# Roboteq_IO_Board_V2.net
KiCad netlist of a schematic drawn in EAGLE
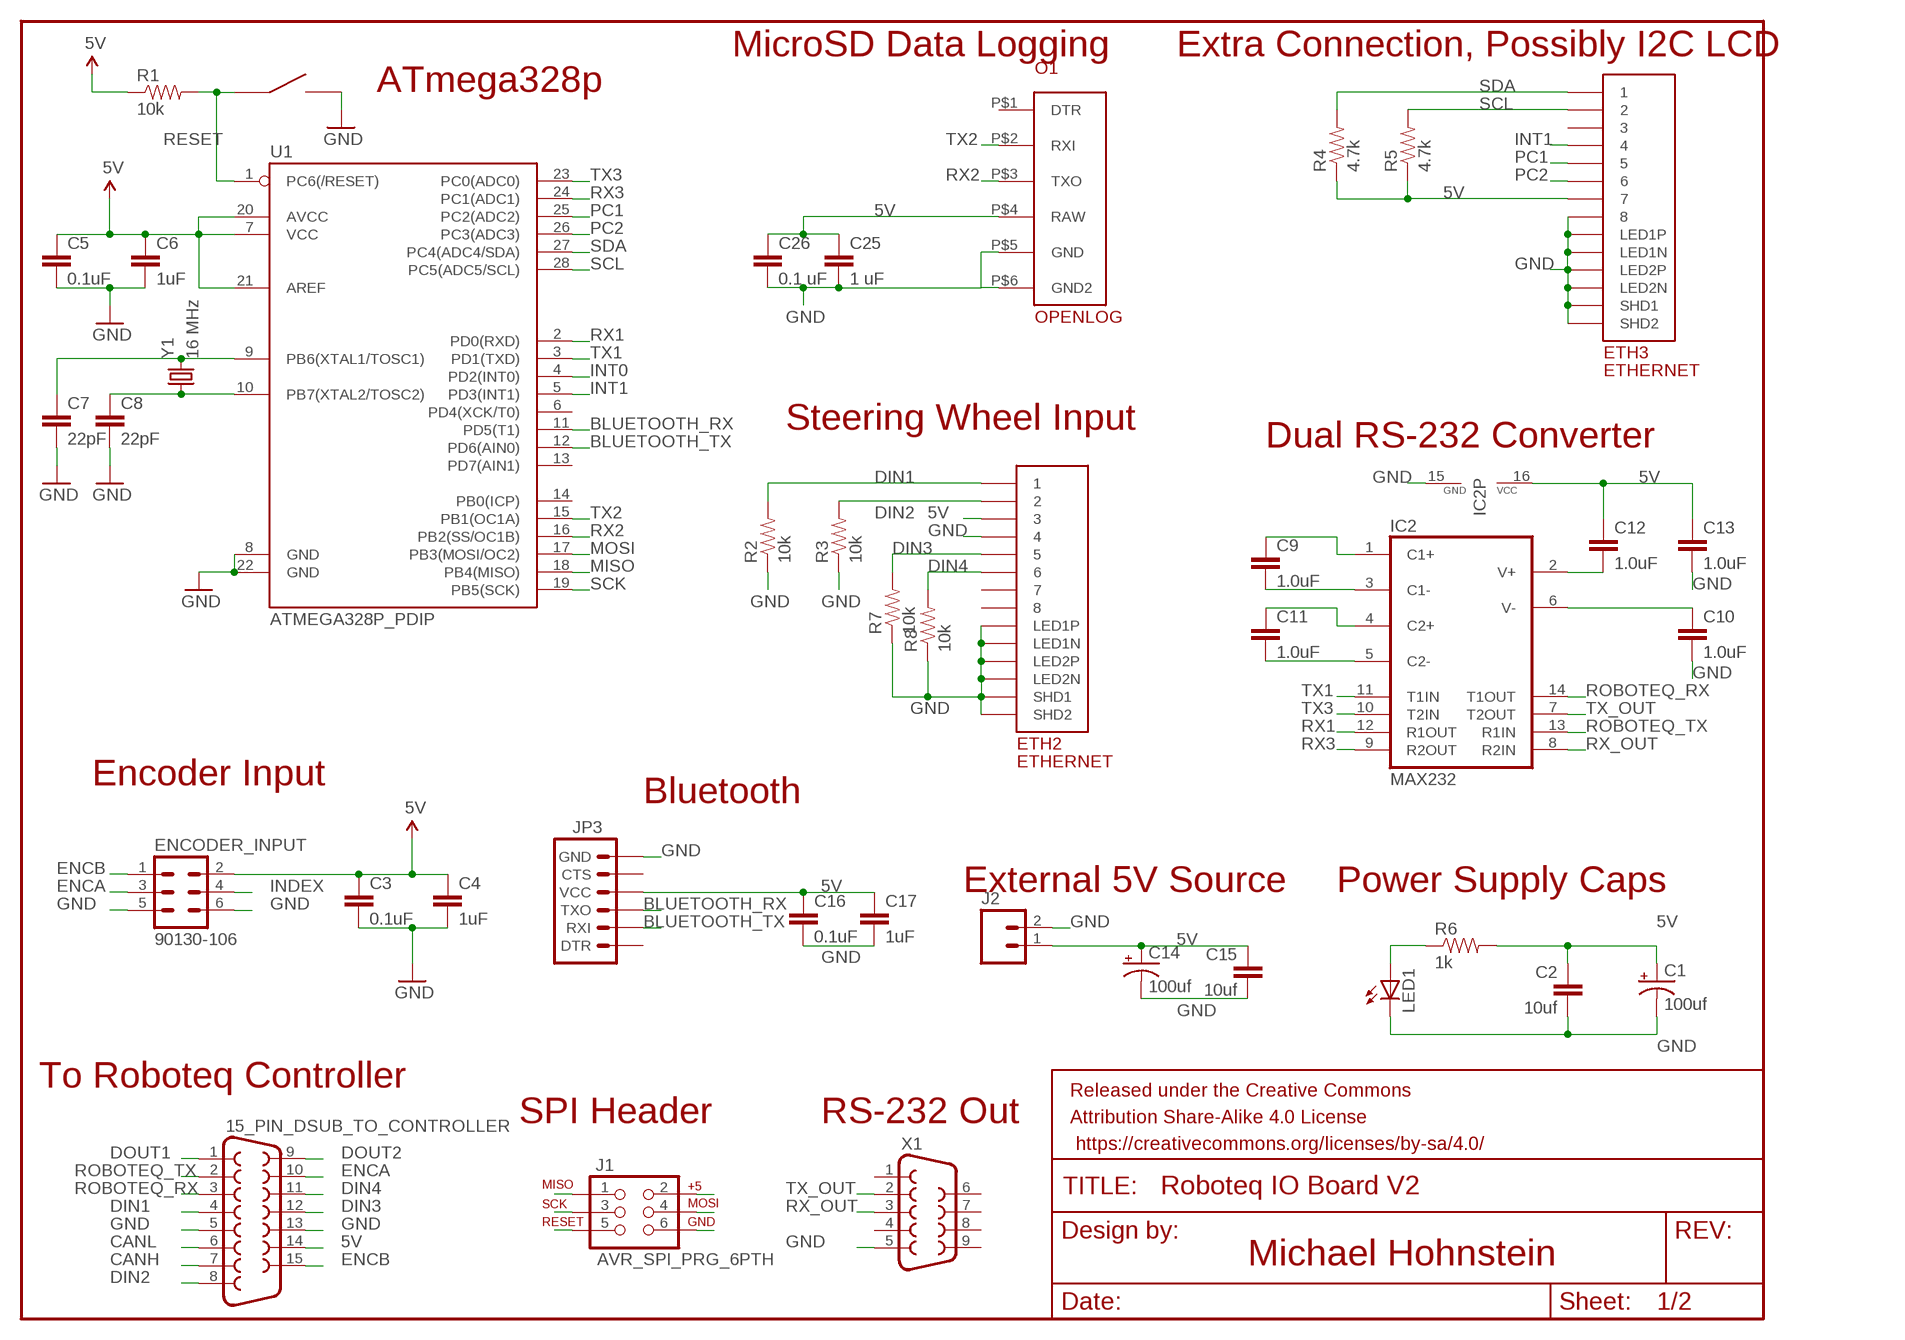
[diagram p0: schematic, sheet 1]
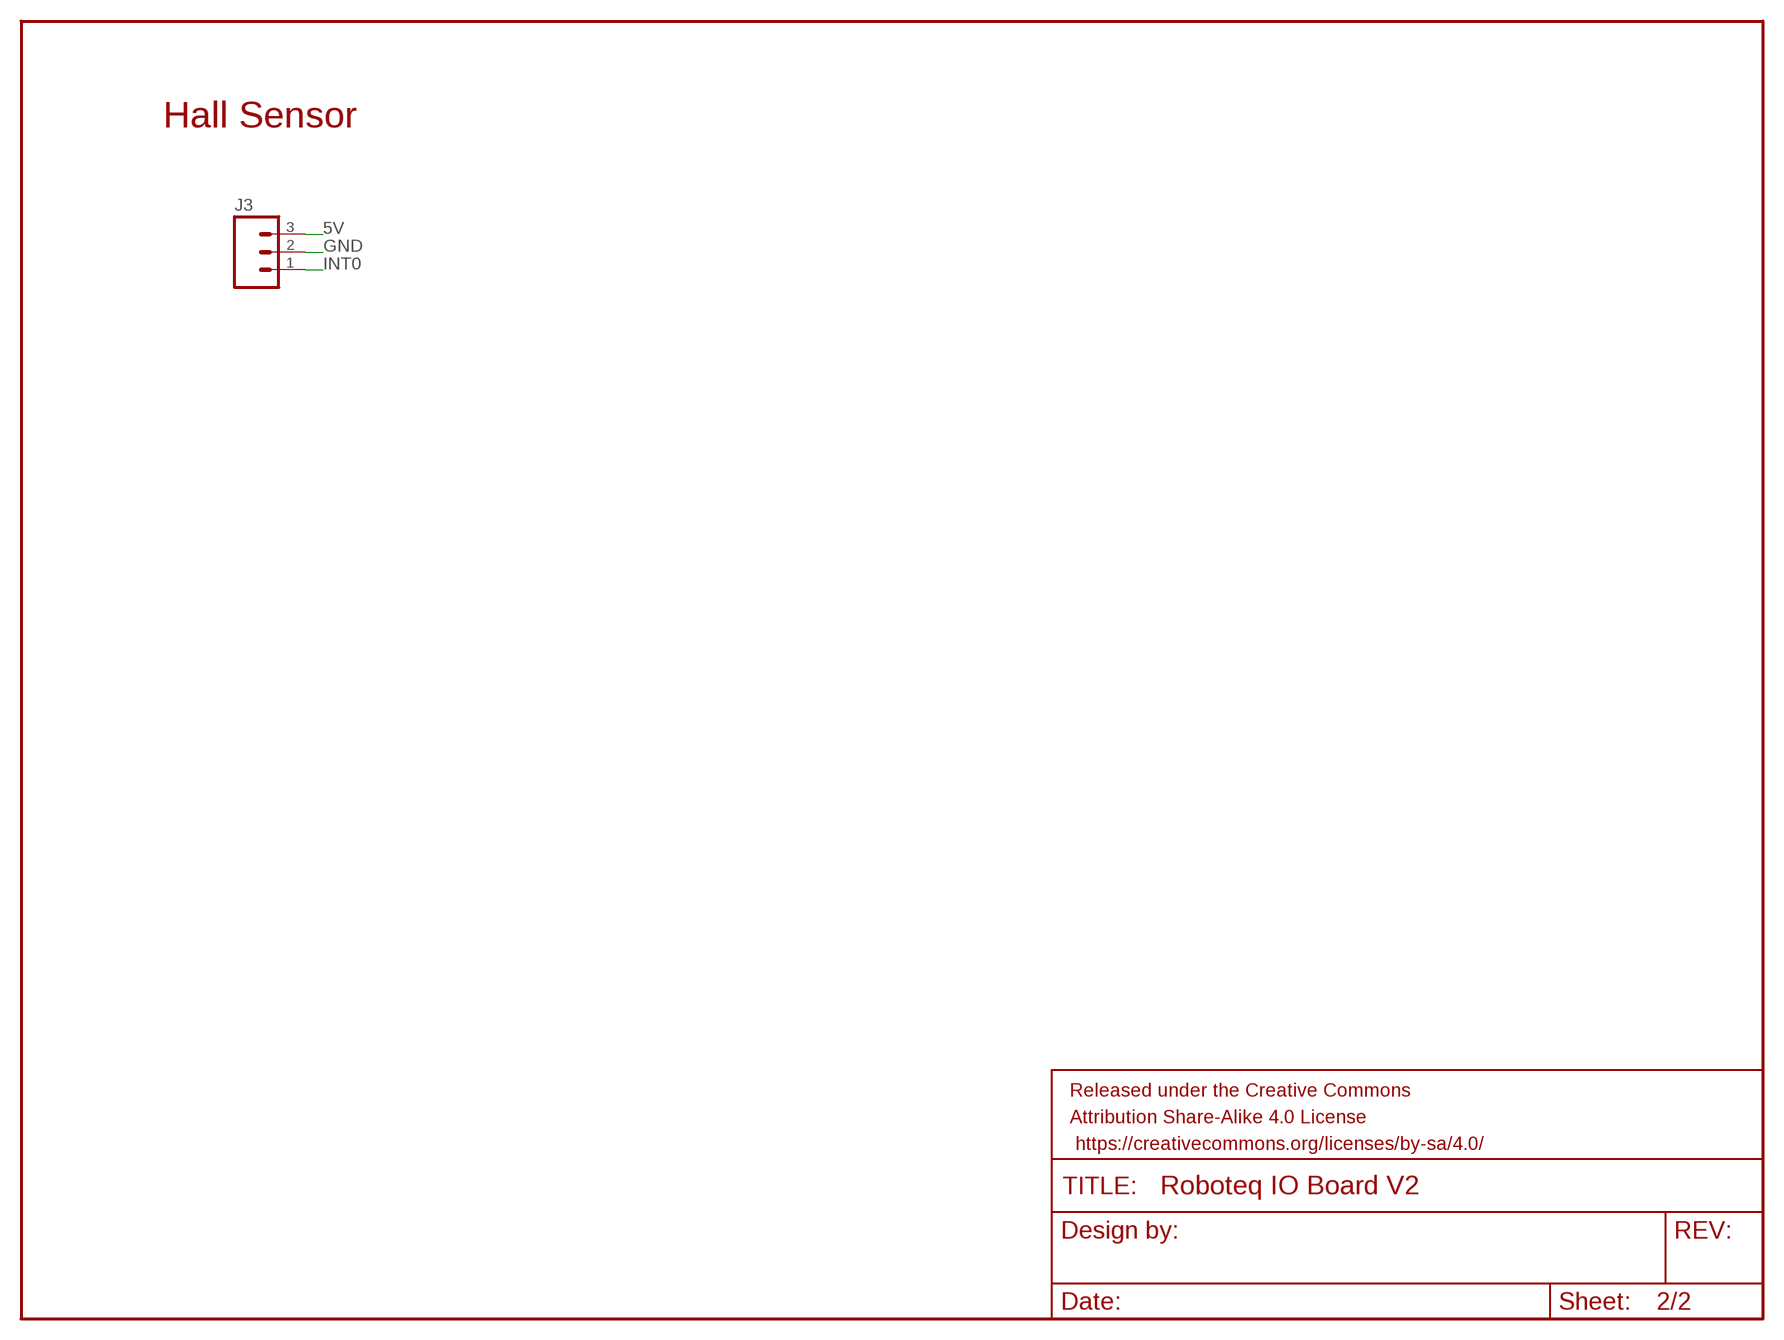
[diagram p1: schematic, sheet 2]

(export (version "E")
  (design (tool "Eeschema 10.0.6"))
  (components
    (comp (ref "15_PIN_DSUB_TO_CONTROLLER")
      (value "F15HP")
      (footprint "eagle-import:F15HP")
      (libsource (lib "eagle-import") (part "F15HP"))
    )
    (comp (ref "C1")
      (value "100uf")
      (footprint "eagle-import:PANASONIC_C")
      (libsource (lib "eagle-import") (part "CAP_POLC"))
    )
    (comp (ref "C2")
      (value "10uf")
      (footprint "eagle-import:0805")
      (libsource (lib "eagle-import") (part "CAP0805"))
    )
    (comp (ref "C3")
      (value "0.1uF")
      (footprint "eagle-import:0805")
      (libsource (lib "eagle-import") (part "CAP0805"))
    )
    (comp (ref "C4")
      (value "1uF")
      (footprint "eagle-import:0805")
      (libsource (lib "eagle-import") (part "CAP0805"))
    )
    (comp (ref "C5")
      (value "0.1uF")
      (footprint "eagle-import:0805")
      (libsource (lib "eagle-import") (part "CAP0805"))
    )
    (comp (ref "C6")
      (value "1uF")
      (footprint "eagle-import:0805")
      (libsource (lib "eagle-import") (part "CAP0805"))
    )
    (comp (ref "C7")
      (value "22pF")
      (footprint "eagle-import:0805")
      (libsource (lib "eagle-import") (part "SparkFun-Passives_CAP0805"))
    )
    (comp (ref "C8")
      (value "22pF")
      (footprint "eagle-import:0805")
      (libsource (lib "eagle-import") (part "SparkFun-Passives_CAP0805"))
    )
    (comp (ref "C9")
      (value "1.0uF")
      (footprint "eagle-import:0805")
      (libsource (lib "eagle-import") (part "CAP0805"))
    )
    (comp (ref "C10")
      (value "1.0uF")
      (footprint "eagle-import:0805")
      (libsource (lib "eagle-import") (part "CAP0805"))
    )
    (comp (ref "C11")
      (value "1.0uF")
      (footprint "eagle-import:0805")
      (libsource (lib "eagle-import") (part "CAP0805"))
    )
    (comp (ref "C12")
      (value "1.0uF")
      (footprint "eagle-import:0805")
      (libsource (lib "eagle-import") (part "CAP0805"))
    )
    (comp (ref "C13")
      (value "1.0uF")
      (footprint "eagle-import:0805")
      (libsource (lib "eagle-import") (part "CAP0805"))
    )
    (comp (ref "C14")
      (value "100uf")
      (footprint "eagle-import:PANASONIC_C")
      (libsource (lib "eagle-import") (part "CAP_POLC"))
    )
    (comp (ref "C15")
      (value "10uf")
      (footprint "eagle-import:0805")
      (libsource (lib "eagle-import") (part "CAP0805"))
    )
    (comp (ref "C16")
      (value "0.1uF")
      (footprint "eagle-import:0805")
      (libsource (lib "eagle-import") (part "CAP0805"))
    )
    (comp (ref "C17")
      (value "1uF")
      (footprint "eagle-import:0805")
      (libsource (lib "eagle-import") (part "CAP0805"))
    )
    (comp (ref "C25")
      (value "1 uF")
      (footprint "eagle-import:0805")
      (libsource (lib "eagle-import") (part "CAP0805"))
    )
    (comp (ref "C26")
      (value "0.1 uF")
      (footprint "eagle-import:0805")
      (libsource (lib "eagle-import") (part "CAP0805"))
    )
    (comp (ref "ENCODER_INPUT")
      (value "90130-106")
      (footprint "eagle-import:90130-1_06")
      (libsource (lib "eagle-import") (part "90130-1?06"))
    )
    (comp (ref "ETH2")
      (value "ETHERNET")
      (footprint "eagle-import:A122645-ND")
      (libsource (lib "eagle-import") (part "ETHERNET"))
    )
    (comp (ref "ETH3")
      (value "ETHERNET")
      (footprint "eagle-import:A122645-ND")
      (libsource (lib "eagle-import") (part "ETHERNET"))
    )
    (comp (ref "FRAME2")
      (value "FRAME-LETTER")
      (footprint "eagle-import:CREATIVE_COMMONS")
      (libsource (lib "eagle-import") (part "FRAME-LETTER"))
    )
    (comp (ref "IC2")
      (value "MAX232")
      (footprint "eagle-import:DIL16")
      (fields (field (name "MF") "MAXIM") (field (name "MPN") "MAX232ACPE+"))
      (libsource (lib "eagle-import") (part "MAX232"))
    )
    (comp (ref "J1")
      (value "AVR_SPI_PRG_6PTH")
      (footprint "eagle-import:2X3")
      (libsource (lib "eagle-import") (part "AVR_SPI_PRG_6PTH"))
    )
    (comp (ref "J2")
      (value "M02PTH")
      (footprint "eagle-import:1X02")
      (libsource (lib "eagle-import") (part "M02PTH"))
    )
    (comp (ref "JP3")
      (value "ARDUINO_SERIAL_PROGRAMPTH")
      (footprint "eagle-import:1X06")
      (libsource (lib "eagle-import") (part "ARDUINO_SERIAL_PROGRAMPTH"))
    )
    (comp (ref "LED1")
      (value "LEDCHIP-LED0805")
      (footprint "eagle-import:CHIP-LED0805")
      (libsource (lib "eagle-import") (part "LEDCHIP-LED0805"))
    )
    (comp (ref "O1")
      (value "OPENLOG")
      (footprint "eagle-import:OPENLOG")
      (libsource (lib "eagle-import") (part "OPENLOG"))
    )
    (comp (ref "R1")
      (value "10k")
      (footprint "eagle-import:0805")
      (libsource (lib "eagle-import") (part "RESISTOR0805-RES"))
    )
    (comp (ref "R2")
      (value "10k")
      (footprint "eagle-import:0805")
      (libsource (lib "eagle-import") (part "RESISTOR0805-RES"))
    )
    (comp (ref "R3")
      (value "10k")
      (footprint "eagle-import:0805")
      (libsource (lib "eagle-import") (part "RESISTOR0805-RES"))
    )
    (comp (ref "R4")
      (value "4.7k")
      (footprint "eagle-import:0805")
      (libsource (lib "eagle-import") (part "RESISTOR0805-RES"))
    )
    (comp (ref "R5")
      (value "4.7k")
      (footprint "eagle-import:0805")
      (libsource (lib "eagle-import") (part "RESISTOR0805-RES"))
    )
    (comp (ref "R6")
      (value "1k")
      (footprint "eagle-import:0805")
      (libsource (lib "eagle-import") (part "RESISTOR0805-RES"))
    )
    (comp (ref "R7")
      (value "10k")
      (footprint "eagle-import:0805")
      (libsource (lib "eagle-import") (part "RESISTOR0805-RES"))
    )
    (comp (ref "R8")
      (value "10k")
      (footprint "eagle-import:0805")
      (libsource (lib "eagle-import") (part "RESISTOR0805-RES"))
    )
    (comp (ref "U$3")
      (value "EG4621CT-ND")
      (footprint "eagle-import:EG4621CT-ND")
      (libsource (lib "eagle-import") (part "EG4621CT-ND"))
    )
    (comp (ref "U1")
      (value "ATMEGA328P_PDIP")
      (footprint "eagle-import:DIL28-3")
      (libsource (lib "eagle-import") (part "ATMEGA328P_PDIP"))
    )
    (comp (ref "X1")
      (value "F09HP")
      (footprint "eagle-import:F09HP")
      (libsource (lib "eagle-import") (part "F09HP"))
    )
    (comp (ref "Y1")
      (value "16 MHz")
      (footprint "eagle-import:HC49US")
      (libsource (lib "eagle-import") (part "CRYSTALHC49US"))
    )
    (comp (ref "FRAME1")
      (value "FRAME-LETTER")
      (footprint "eagle-import:CREATIVE_COMMONS")
      (libsource (lib "eagle-import") (part "FRAME-LETTER"))
    )
    (comp (ref "J3")
      (value "M03PTH")
      (footprint "eagle-import:1X03")
      (libsource (lib "eagle-import") (part "M03PTH"))
    )
  )
  (nets
    (net (code "1") (name "5V") (class "Default")
      (node (ref "15_PIN_DSUB_TO_CONTROLLER") (pin "14") (pinfunction "14_14") (pintype "passive"))
      (node (ref "C1") (pin "+") (pinfunction "+_+") (pintype "passive"))
      (node (ref "C12") (pin "1") (pinfunction "1_1") (pintype "passive"))
      (node (ref "C13") (pin "1") (pinfunction "1_1") (pintype "passive"))
      (node (ref "C14") (pin "+") (pinfunction "+_+") (pintype "passive"))
      (node (ref "C15") (pin "1") (pinfunction "1_1") (pintype "passive"))
      (node (ref "C16") (pin "1") (pinfunction "1_1") (pintype "passive"))
      (node (ref "C17") (pin "1") (pinfunction "1_1") (pintype "passive"))
      (node (ref "C2") (pin "1") (pinfunction "1_1") (pintype "passive"))
      (node (ref "C25") (pin "1") (pinfunction "1_1") (pintype "passive"))
      (node (ref "C26") (pin "1") (pinfunction "1_1") (pintype "passive"))
      (node (ref "C3") (pin "1") (pinfunction "1_1") (pintype "passive"))
      (node (ref "C4") (pin "1") (pinfunction "1_1") (pintype "passive"))
      (node (ref "C5") (pin "1") (pinfunction "1_1") (pintype "passive"))
      (node (ref "C6") (pin "1") (pinfunction "1_1") (pintype "passive"))
      (node (ref "ENCODER_INPUT") (pin "2") (pinfunction "2_2") (pintype "passive"))
      (node (ref "ETH2") (pin "P$3") (pinfunction "3_P$3") (pintype "bidirectional"))
      (node (ref "ETH3") (pin "P$7") (pinfunction "7_P$7") (pintype "bidirectional"))
      (node (ref "IC2") (pin "16") (pinfunction "VCC_16") (pintype "power_in"))
      (node (ref "J1") (pin "2") (pinfunction "2_2") (pintype "passive"))
      (node (ref "J2") (pin "1") (pinfunction "1_1") (pintype "passive"))
      (node (ref "J3") (pin "3") (pinfunction "3_3") (pintype "passive"))
      (node (ref "JP3") (pin "4") (pinfunction "VCC_4") (pintype "passive"))
      (node (ref "O1") (pin "P$4") (pinfunction "RAW_P$4") (pintype "bidirectional"))
      (node (ref "R1") (pin "1") (pinfunction "1_1") (pintype "passive"))
      (node (ref "R4") (pin "1") (pinfunction "1_1") (pintype "passive"))
      (node (ref "R5") (pin "1") (pinfunction "1_1") (pintype "passive"))
      (node (ref "R6") (pin "2") (pinfunction "2_2") (pintype "passive"))
      (node (ref "U1") (pin "20") (pinfunction "AVCC_20") (pintype "bidirectional"))
      (node (ref "U1") (pin "21") (pinfunction "AREF_21") (pintype "bidirectional"))
      (node (ref "U1") (pin "7") (pinfunction "VCC_7") (pintype "bidirectional"))
    )
    (net (code "2") (name "BLUETOOTH_RX") (class "Default")
      (node (ref "JP3") (pin "3") (pinfunction "TXO_3") (pintype "passive"))
      (node (ref "U1") (pin "11") (pinfunction "PD5(T1)_11") (pintype "bidirectional"))
    )
    (net (code "3") (name "BLUETOOTH_TX") (class "Default")
      (node (ref "JP3") (pin "2") (pinfunction "RXI_2") (pintype "passive"))
      (node (ref "U1") (pin "12") (pinfunction "PD6(AIN0)_12") (pintype "bidirectional"))
    )
    (net (code "4") (name "CANH") (class "Default")
      (node (ref "15_PIN_DSUB_TO_CONTROLLER") (pin "7") (pinfunction "7_7") (pintype "passive"))
    )
    (net (code "5") (name "CANL") (class "Default")
      (node (ref "15_PIN_DSUB_TO_CONTROLLER") (pin "6") (pinfunction "6_6") (pintype "passive"))
    )
    (net (code "6") (name "DIN1") (class "Default")
      (node (ref "15_PIN_DSUB_TO_CONTROLLER") (pin "4") (pinfunction "4_4") (pintype "passive"))
      (node (ref "ETH2") (pin "P$1") (pinfunction "1_P$1") (pintype "bidirectional"))
      (node (ref "R2") (pin "2") (pinfunction "2_2") (pintype "passive"))
    )
    (net (code "7") (name "DIN2") (class "Default")
      (node (ref "15_PIN_DSUB_TO_CONTROLLER") (pin "8") (pinfunction "8_8") (pintype "passive"))
      (node (ref "ETH2") (pin "P$2") (pinfunction "2_P$2") (pintype "bidirectional"))
      (node (ref "R3") (pin "2") (pinfunction "2_2") (pintype "passive"))
    )
    (net (code "8") (name "DIN3") (class "Default")
      (node (ref "15_PIN_DSUB_TO_CONTROLLER") (pin "12") (pinfunction "12_12") (pintype "passive"))
      (node (ref "ETH2") (pin "P$5") (pinfunction "5_P$5") (pintype "bidirectional"))
      (node (ref "R7") (pin "2") (pinfunction "2_2") (pintype "passive"))
    )
    (net (code "9") (name "DIN4") (class "Default")
      (node (ref "15_PIN_DSUB_TO_CONTROLLER") (pin "11") (pinfunction "11_11") (pintype "passive"))
      (node (ref "ETH2") (pin "P$6") (pinfunction "6_P$6") (pintype "bidirectional"))
      (node (ref "R8") (pin "2") (pinfunction "2_2") (pintype "passive"))
    )
    (net (code "10") (name "DOUT1") (class "Default")
      (node (ref "15_PIN_DSUB_TO_CONTROLLER") (pin "1") (pinfunction "1_1") (pintype "passive"))
    )
    (net (code "11") (name "DOUT2") (class "Default")
      (node (ref "15_PIN_DSUB_TO_CONTROLLER") (pin "9") (pinfunction "9_9") (pintype "passive"))
    )
    (net (code "12") (name "ENCA") (class "Default")
      (node (ref "15_PIN_DSUB_TO_CONTROLLER") (pin "10") (pinfunction "10_10") (pintype "passive"))
      (node (ref "ENCODER_INPUT") (pin "3") (pinfunction "3_3") (pintype "passive"))
    )
    (net (code "13") (name "ENCB") (class "Default")
      (node (ref "15_PIN_DSUB_TO_CONTROLLER") (pin "15") (pinfunction "15_15") (pintype "passive"))
      (node (ref "ENCODER_INPUT") (pin "1") (pinfunction "1_1") (pintype "passive"))
    )
    (net (code "14") (name "GND") (class "Default")
      (node (ref "15_PIN_DSUB_TO_CONTROLLER") (pin "13") (pinfunction "13_13") (pintype "passive"))
      (node (ref "15_PIN_DSUB_TO_CONTROLLER") (pin "5") (pinfunction "5_5") (pintype "passive"))
      (node (ref "C1") (pin "-") (pinfunction "-_-") (pintype "passive"))
      (node (ref "C10") (pin "2") (pinfunction "2_2") (pintype "passive"))
      (node (ref "C13") (pin "2") (pinfunction "2_2") (pintype "passive"))
      (node (ref "C14") (pin "-") (pinfunction "-_-") (pintype "passive"))
      (node (ref "C15") (pin "2") (pinfunction "2_2") (pintype "passive"))
      (node (ref "C16") (pin "2") (pinfunction "2_2") (pintype "passive"))
      (node (ref "C17") (pin "2") (pinfunction "2_2") (pintype "passive"))
      (node (ref "C2") (pin "2") (pinfunction "2_2") (pintype "passive"))
      (node (ref "C25") (pin "2") (pinfunction "2_2") (pintype "passive"))
      (node (ref "C26") (pin "2") (pinfunction "2_2") (pintype "passive"))
      (node (ref "C3") (pin "2") (pinfunction "2_2") (pintype "passive"))
      (node (ref "C4") (pin "2") (pinfunction "2_2") (pintype "passive"))
      (node (ref "C5") (pin "2") (pinfunction "2_2") (pintype "passive"))
      (node (ref "C6") (pin "2") (pinfunction "2_2") (pintype "passive"))
      (node (ref "C7") (pin "2") (pinfunction "2_2") (pintype "passive"))
      (node (ref "C8") (pin "2") (pinfunction "2_2") (pintype "passive"))
      (node (ref "ENCODER_INPUT") (pin "5") (pinfunction "5_5") (pintype "passive"))
      (node (ref "ENCODER_INPUT") (pin "6") (pinfunction "6_6") (pintype "passive"))
      (node (ref "ETH2") (pin "P$10") (pinfunction "LED1P_P$10") (pintype "bidirectional"))
      (node (ref "ETH2") (pin "P$11") (pinfunction "LED2N_P$11") (pintype "bidirectional"))
      (node (ref "ETH2") (pin "P$12") (pinfunction "LED2P_P$12") (pintype "bidirectional"))
      (node (ref "ETH2") (pin "P$13") (pinfunction "SHD1_P$13") (pintype "bidirectional"))
      (node (ref "ETH2") (pin "P$14") (pinfunction "SHD2_P$14") (pintype "bidirectional"))
      (node (ref "ETH2") (pin "P$4") (pinfunction "4_P$4") (pintype "bidirectional"))
      (node (ref "ETH2") (pin "P$9") (pinfunction "LED1N_P$9") (pintype "bidirectional"))
      (node (ref "ETH3") (pin "P$10") (pinfunction "LED1P_P$10") (pintype "bidirectional"))
      (node (ref "ETH3") (pin "P$11") (pinfunction "LED2N_P$11") (pintype "bidirectional"))
      (node (ref "ETH3") (pin "P$12") (pinfunction "LED2P_P$12") (pintype "bidirectional"))
      (node (ref "ETH3") (pin "P$13") (pinfunction "SHD1_P$13") (pintype "bidirectional"))
      (node (ref "ETH3") (pin "P$14") (pinfunction "SHD2_P$14") (pintype "bidirectional"))
      (node (ref "ETH3") (pin "P$8") (pinfunction "8_P$8") (pintype "bidirectional"))
      (node (ref "ETH3") (pin "P$9") (pinfunction "LED1N_P$9") (pintype "bidirectional"))
      (node (ref "IC2") (pin "15") (pinfunction "GND_15") (pintype "power_in"))
      (node (ref "J1") (pin "6") (pinfunction "6_6") (pintype "passive"))
      (node (ref "J2") (pin "2") (pinfunction "2_2") (pintype "passive"))
      (node (ref "J3") (pin "2") (pinfunction "2_2") (pintype "passive"))
      (node (ref "JP3") (pin "6") (pinfunction "GND_6") (pintype "passive"))
      (node (ref "LED1") (pin "C") (pinfunction "C_C") (pintype "passive"))
      (node (ref "O1") (pin "P$5") (pinfunction "GND_P$5") (pintype "bidirectional"))
      (node (ref "O1") (pin "P$6") (pinfunction "GND2_P$6") (pintype "bidirectional"))
      (node (ref "R2") (pin "1") (pinfunction "1_1") (pintype "passive"))
      (node (ref "R3") (pin "1") (pinfunction "1_1") (pintype "passive"))
      (node (ref "R7") (pin "1") (pinfunction "1_1") (pintype "passive"))
      (node (ref "R8") (pin "1") (pinfunction "1_1") (pintype "passive"))
      (node (ref "U$3") (pin "P$3") (pinfunction "P$2_P$3") (pintype "bidirectional"))
      (node (ref "U$3") (pin "P$4") (pinfunction "P$2_P$4") (pintype "bidirectional"))
      (node (ref "U1") (pin "22") (pinfunction "GND_22") (pintype "bidirectional"))
      (node (ref "U1") (pin "8") (pinfunction "GND_8") (pintype "bidirectional"))
      (node (ref "X1") (pin "5") (pinfunction "5_5") (pintype "passive"))
    )
    (net (code "15") (name "INDEX") (class "Default")
      (node (ref "ENCODER_INPUT") (pin "4") (pinfunction "4_4") (pintype "passive"))
    )
    (net (code "16") (name "INT0") (class "Default")
      (node (ref "J3") (pin "1") (pinfunction "1_1") (pintype "passive"))
      (node (ref "U1") (pin "4") (pinfunction "PD2(INT0)_4") (pintype "bidirectional"))
    )
    (net (code "17") (name "INT1") (class "Default")
      (node (ref "ETH3") (pin "P$4") (pinfunction "4_P$4") (pintype "bidirectional"))
      (node (ref "U1") (pin "5") (pinfunction "PD3(INT1)_5") (pintype "bidirectional"))
    )
    (net (code "18") (name "MISO") (class "Default")
      (node (ref "J1") (pin "1") (pinfunction "1_1") (pintype "passive"))
      (node (ref "U1") (pin "18") (pinfunction "PB4(MISO)_18") (pintype "bidirectional"))
    )
    (net (code "19") (name "MOSI") (class "Default")
      (node (ref "J1") (pin "4") (pinfunction "4_4") (pintype "passive"))
      (node (ref "U1") (pin "17") (pinfunction "PB3(MOSI/OC2)_17") (pintype "bidirectional"))
    )
    (net (code "20") (name "Net-(IC2A-C1+)") (class "Default")
      (node (ref "C9") (pin "1") (pinfunction "1_1") (pintype "passive"))
      (node (ref "IC2") (pin "1") (pinfunction "C1+_1") (pintype "bidirectional"))
    )
    (net (code "21") (name "Net-(IC2A-C1-)") (class "Default")
      (node (ref "C9") (pin "2") (pinfunction "2_2") (pintype "passive"))
      (node (ref "IC2") (pin "3") (pinfunction "C1-_3") (pintype "bidirectional"))
    )
    (net (code "22") (name "Net-(IC2A-C2+)") (class "Default")
      (node (ref "C11") (pin "1") (pinfunction "1_1") (pintype "passive"))
      (node (ref "IC2") (pin "4") (pinfunction "C2+_4") (pintype "bidirectional"))
    )
    (net (code "23") (name "Net-(IC2A-C2-)") (class "Default")
      (node (ref "C11") (pin "2") (pinfunction "2_2") (pintype "passive"))
      (node (ref "IC2") (pin "5") (pinfunction "C2-_5") (pintype "bidirectional"))
    )
    (net (code "24") (name "Net-(IC2A-V+)") (class "Default")
      (node (ref "C12") (pin "2") (pinfunction "2_2") (pintype "passive"))
      (node (ref "IC2") (pin "2") (pinfunction "V+_2") (pintype "bidirectional"))
    )
    (net (code "25") (name "Net-(IC2A-V-)") (class "Default")
      (node (ref "C10") (pin "1") (pinfunction "1_1") (pintype "passive"))
      (node (ref "IC2") (pin "6") (pinfunction "V-_6") (pintype "bidirectional"))
    )
    (net (code "26") (name "Net-(LED1-PadA)") (class "Default")
      (node (ref "LED1") (pin "A") (pinfunction "A_A") (pintype "passive"))
      (node (ref "R6") (pin "1") (pinfunction "1_1") (pintype "passive"))
    )
    (net (code "27") (name "Net-(U1-PB6(XTAL1{slash}TOSC1))") (class "Default")
      (node (ref "C7") (pin "1") (pinfunction "1_1") (pintype "passive"))
      (node (ref "U1") (pin "9") (pinfunction "PB6(XTAL1/TOSC1)_9") (pintype "bidirectional"))
      (node (ref "Y1") (pin "2") (pinfunction "2_2") (pintype "passive"))
    )
    (net (code "28") (name "Net-(U1-PB7(XTAL2{slash}TOSC2))") (class "Default")
      (node (ref "C8") (pin "1") (pinfunction "1_1") (pintype "passive"))
      (node (ref "U1") (pin "10") (pinfunction "PB7(XTAL2/TOSC2)_10") (pintype "bidirectional"))
      (node (ref "Y1") (pin "1") (pinfunction "1_1") (pintype "passive"))
    )
    (net (code "29") (name "PC1") (class "Default")
      (node (ref "ETH3") (pin "P$5") (pinfunction "5_P$5") (pintype "bidirectional"))
      (node (ref "U1") (pin "25") (pinfunction "PC2(ADC2)_25") (pintype "bidirectional"))
    )
    (net (code "30") (name "PC2") (class "Default")
      (node (ref "ETH3") (pin "P$6") (pinfunction "6_P$6") (pintype "bidirectional"))
      (node (ref "U1") (pin "26") (pinfunction "PC3(ADC3)_26") (pintype "bidirectional"))
    )
    (net (code "31") (name "RESET") (class "Default")
      (node (ref "J1") (pin "5") (pinfunction "5_5") (pintype "passive"))
      (node (ref "R1") (pin "2") (pinfunction "2_2") (pintype "passive"))
      (node (ref "U$3") (pin "P$1") (pinfunction "P$1_P$1") (pintype "bidirectional"))
      (node (ref "U$3") (pin "P$2") (pinfunction "P$1_P$2") (pintype "bidirectional"))
      (node (ref "U1") (pin "1") (pinfunction "PC6(/RESET)_1") (pintype "bidirectional"))
    )
    (net (code "32") (name "ROBOTEQ_RX") (class "Default")
      (node (ref "15_PIN_DSUB_TO_CONTROLLER") (pin "3") (pinfunction "3_3") (pintype "passive"))
      (node (ref "IC2") (pin "14") (pinfunction "T1OUT_14") (pintype "output"))
    )
    (net (code "33") (name "ROBOTEQ_TX") (class "Default")
      (node (ref "15_PIN_DSUB_TO_CONTROLLER") (pin "2") (pinfunction "2_2") (pintype "passive"))
      (node (ref "IC2") (pin "13") (pinfunction "R1IN_13") (pintype "input"))
    )
    (net (code "34") (name "RX1") (class "Default")
      (node (ref "IC2") (pin "12") (pinfunction "R1OUT_12") (pintype "output"))
      (node (ref "U1") (pin "2") (pinfunction "PD0(RXD)_2") (pintype "bidirectional"))
    )
    (net (code "35") (name "RX2") (class "Default")
      (node (ref "O1") (pin "P$3") (pinfunction "TXO_P$3") (pintype "bidirectional"))
      (node (ref "U1") (pin "16") (pinfunction "PB2(SS/OC1B)_16") (pintype "bidirectional"))
    )
    (net (code "36") (name "RX3") (class "Default")
      (node (ref "IC2") (pin "9") (pinfunction "R2OUT_9") (pintype "output"))
      (node (ref "U1") (pin "24") (pinfunction "PC1(ADC1)_24") (pintype "bidirectional"))
    )
    (net (code "37") (name "RX_OUT") (class "Default")
      (node (ref "IC2") (pin "8") (pinfunction "R2IN_8") (pintype "input"))
      (node (ref "X1") (pin "3") (pinfunction "3_3") (pintype "passive"))
    )
    (net (code "38") (name "SCK") (class "Default")
      (node (ref "J1") (pin "3") (pinfunction "3_3") (pintype "passive"))
      (node (ref "U1") (pin "19") (pinfunction "PB5(SCK)_19") (pintype "bidirectional"))
    )
    (net (code "39") (name "SCL") (class "Default")
      (node (ref "ETH3") (pin "P$2") (pinfunction "2_P$2") (pintype "bidirectional"))
      (node (ref "R5") (pin "2") (pinfunction "2_2") (pintype "passive"))
      (node (ref "U1") (pin "28") (pinfunction "PC5(ADC5/SCL)_28") (pintype "bidirectional"))
    )
    (net (code "40") (name "SDA") (class "Default")
      (node (ref "ETH3") (pin "P$1") (pinfunction "1_P$1") (pintype "bidirectional"))
      (node (ref "R4") (pin "2") (pinfunction "2_2") (pintype "passive"))
      (node (ref "U1") (pin "27") (pinfunction "PC4(ADC4/SDA)_27") (pintype "bidirectional"))
    )
    (net (code "41") (name "TX1") (class "Default")
      (node (ref "IC2") (pin "11") (pinfunction "T1IN_11") (pintype "input"))
      (node (ref "U1") (pin "3") (pinfunction "PD1(TXD)_3") (pintype "bidirectional"))
    )
    (net (code "42") (name "TX2") (class "Default")
      (node (ref "O1") (pin "P$2") (pinfunction "RXI_P$2") (pintype "bidirectional"))
      (node (ref "U1") (pin "15") (pinfunction "PB1(OC1A)_15") (pintype "bidirectional"))
    )
    (net (code "43") (name "TX3") (class "Default")
      (node (ref "IC2") (pin "10") (pinfunction "T2IN_10") (pintype "input"))
      (node (ref "U1") (pin "23") (pinfunction "PC0(ADC0)_23") (pintype "bidirectional"))
    )
    (net (code "44") (name "TX_OUT") (class "Default")
      (node (ref "IC2") (pin "7") (pinfunction "T2OUT_7") (pintype "output"))
      (node (ref "X1") (pin "2") (pinfunction "2_2") (pintype "passive"))
    )
    (net (code "45") (name "unconnected-(ETH2-7-PadP$7)") (class "Default")
      (node (ref "ETH2") (pin "P$7") (pinfunction "7_P$7") (pintype "bidirectional"))
    )
    (net (code "46") (name "unconnected-(ETH2-8-PadP$8)") (class "Default")
      (node (ref "ETH2") (pin "P$8") (pinfunction "8_P$8") (pintype "bidirectional"))
    )
    (net (code "47") (name "unconnected-(ETH3-3-PadP$3)") (class "Default")
      (node (ref "ETH3") (pin "P$3") (pinfunction "3_P$3") (pintype "bidirectional"))
    )
    (net (code "48") (name "unconnected-(JP3-CTS-Pad5)") (class "Default")
      (node (ref "JP3") (pin "5") (pinfunction "CTS_5") (pintype "passive"))
    )
    (net (code "49") (name "unconnected-(JP3-DTR-Pad1)") (class "Default")
      (node (ref "JP3") (pin "1") (pinfunction "DTR_1") (pintype "passive"))
    )
    (net (code "50") (name "unconnected-(O1-DTR-PadP$1)") (class "Default")
      (node (ref "O1") (pin "P$1") (pinfunction "DTR_P$1") (pintype "bidirectional"))
    )
    (net (code "51") (name "unconnected-(U1-PB0(ICP)-Pad14)") (class "Default")
      (node (ref "U1") (pin "14") (pinfunction "PB0(ICP)_14") (pintype "bidirectional"))
    )
    (net (code "52") (name "unconnected-(U1-PD4(XCK{slash}T0)-Pad6)") (class "Default")
      (node (ref "U1") (pin "6") (pinfunction "PD4(XCK/T0)_6") (pintype "bidirectional"))
    )
    (net (code "53") (name "unconnected-(U1-PD7(AIN1)-Pad13)") (class "Default")
      (node (ref "U1") (pin "13") (pinfunction "PD7(AIN1)_13") (pintype "bidirectional"))
    )
    (net (code "54") (name "unconnected-(X1-Pad1)") (class "Default")
      (node (ref "X1") (pin "1") (pinfunction "1_1") (pintype "passive"))
    )
    (net (code "55") (name "unconnected-(X1-Pad4)") (class "Default")
      (node (ref "X1") (pin "4") (pinfunction "4_4") (pintype "passive"))
    )
    (net (code "56") (name "unconnected-(X1-Pad6)") (class "Default")
      (node (ref "X1") (pin "6") (pinfunction "6_6") (pintype "passive"))
    )
    (net (code "57") (name "unconnected-(X1-Pad7)") (class "Default")
      (node (ref "X1") (pin "7") (pinfunction "7_7") (pintype "passive"))
    )
    (net (code "58") (name "unconnected-(X1-Pad8)") (class "Default")
      (node (ref "X1") (pin "8") (pinfunction "8_8") (pintype "passive"))
    )
    (net (code "59") (name "unconnected-(X1-Pad9)") (class "Default")
      (node (ref "X1") (pin "9") (pinfunction "9_9") (pintype "passive"))
    )
  )
)
